# GERMO.net
KiCad netlist of a schematic drawn in EAGLE
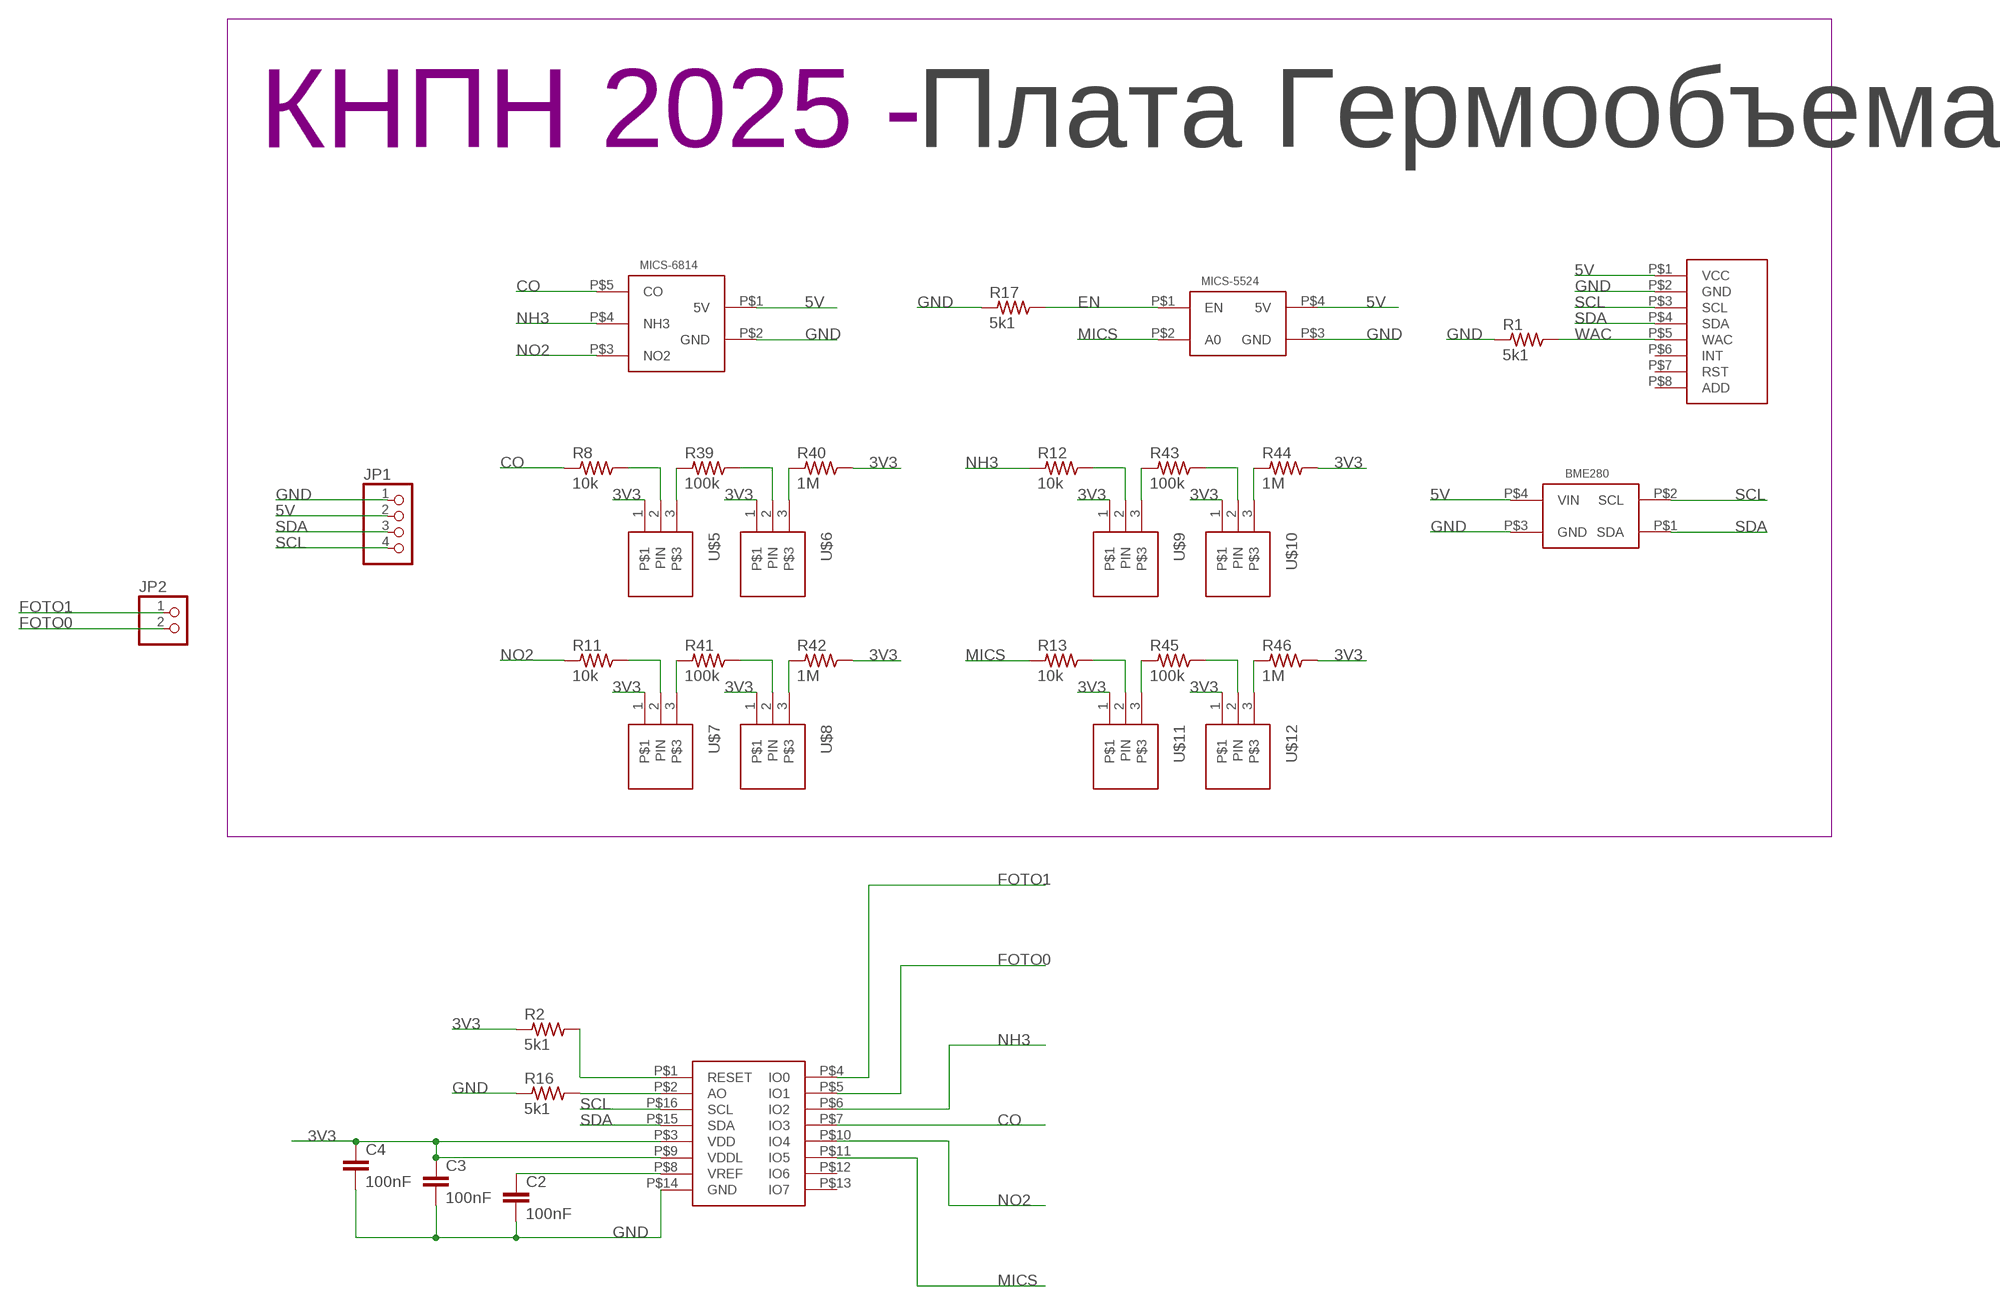
[diagram p0: schematic, sheet 1]

(export (version "E")
  (design (tool "Eeschema 10.0.6"))
  (components
    (comp (ref "BME280")
      (value "BME280BME280-PINS-ONLY")
      (footprint "eagle-import:BME280-PINS-ONLY")
      (libsource (lib "eagle-import") (part "BME280BME280-PINS-ONLY"))
    )
    (comp (ref "C2")
      (value "100nF")
      (footprint "eagle-import:C0603")
      (libsource (lib "eagle-import") (part "C-EUC0603"))
    )
    (comp (ref "C3")
      (value "100nF")
      (footprint "eagle-import:C0603")
      (libsource (lib "eagle-import") (part "C-EUC0603"))
    )
    (comp (ref "C4")
      (value "100nF")
      (footprint "eagle-import:C0603")
      (libsource (lib "eagle-import") (part "C-EUC0603"))
    )
    (comp (ref "CCS811")
      (value "CCS811")
      (footprint "eagle-import:CSS811")
      (libsource (lib "eagle-import") (part "CCS811"))
    )
    (comp (ref "JP1")
      (value "PINHD-1X4")
      (footprint "eagle-import:1X04")
      (libsource (lib "eagle-import") (part "PINHD-1X4"))
    )
    (comp (ref "JP2")
      (value "PINHD-1X2")
      (footprint "eagle-import:1X02")
      (libsource (lib "eagle-import") (part "PINHD-1X2"))
    )
    (comp (ref "MICS-5524")
      (value "MICS_5524")
      (footprint "eagle-import:MICS-5524")
      (libsource (lib "eagle-import") (part "MICS_5524"))
    )
    (comp (ref "MICS-6814")
      (value "MICS-6814")
      (footprint "eagle-import:MICS-6814")
      (libsource (lib "eagle-import") (part "MICS-6814"))
    )
    (comp (ref "R1")
      (value "5k1")
      (footprint "eagle-import:R0603")
      (libsource (lib "eagle-import") (part "R-US_R0603"))
    )
    (comp (ref "R2")
      (value "5k1")
      (footprint "eagle-import:R0603")
      (libsource (lib "eagle-import") (part "R-US_R0603"))
    )
    (comp (ref "R8")
      (value "10k")
      (footprint "eagle-import:R0603")
      (libsource (lib "eagle-import") (part "R-US_R0603"))
    )
    (comp (ref "R11")
      (value "10k")
      (footprint "eagle-import:R0603")
      (libsource (lib "eagle-import") (part "R-US_R0603"))
    )
    (comp (ref "R12")
      (value "10k")
      (footprint "eagle-import:R0603")
      (libsource (lib "eagle-import") (part "R-US_R0603"))
    )
    (comp (ref "R13")
      (value "10k")
      (footprint "eagle-import:R0603")
      (libsource (lib "eagle-import") (part "R-US_R0603"))
    )
    (comp (ref "R16")
      (value "5k1")
      (footprint "eagle-import:R0603")
      (libsource (lib "eagle-import") (part "R-US_R0603"))
    )
    (comp (ref "R17")
      (value "5k1")
      (footprint "eagle-import:R0603")
      (libsource (lib "eagle-import") (part "R-US_R0603"))
    )
    (comp (ref "R39")
      (value "100k")
      (footprint "eagle-import:R0603")
      (libsource (lib "eagle-import") (part "R-US_R0603"))
    )
    (comp (ref "R40")
      (value "1M")
      (footprint "eagle-import:R0603")
      (libsource (lib "eagle-import") (part "R-US_R0603"))
    )
    (comp (ref "R41")
      (value "100k")
      (footprint "eagle-import:R0603")
      (libsource (lib "eagle-import") (part "R-US_R0603"))
    )
    (comp (ref "R42")
      (value "1M")
      (footprint "eagle-import:R0603")
      (libsource (lib "eagle-import") (part "R-US_R0603"))
    )
    (comp (ref "R43")
      (value "100k")
      (footprint "eagle-import:R0603")
      (libsource (lib "eagle-import") (part "R-US_R0603"))
    )
    (comp (ref "R44")
      (value "1M")
      (footprint "eagle-import:R0603")
      (libsource (lib "eagle-import") (part "R-US_R0603"))
    )
    (comp (ref "R45")
      (value "100k")
      (footprint "eagle-import:R0603")
      (libsource (lib "eagle-import") (part "R-US_R0603"))
    )
    (comp (ref "R46")
      (value "1M")
      (footprint "eagle-import:R0603")
      (libsource (lib "eagle-import") (part "R-US_R0603"))
    )
    (comp (ref "U$2")
      (value "Плата Гермообъема")
      (footprint "eagle-import:LOGO")
      (libsource (lib "eagle-import") (part "LOGOPCB-{dblquote}{dblquote}"))
    )
    (comp (ref "U$5")
      (value "CONNECT_3")
      (footprint "eagle-import:CONNECT_3")
      (libsource (lib "eagle-import") (part "CONNECT_3"))
    )
    (comp (ref "U$6")
      (value "CONNECT_3")
      (footprint "eagle-import:CONNECT_3")
      (libsource (lib "eagle-import") (part "CONNECT_3"))
    )
    (comp (ref "U$7")
      (value "CONNECT_3")
      (footprint "eagle-import:CONNECT_3")
      (libsource (lib "eagle-import") (part "CONNECT_3"))
    )
    (comp (ref "U$8")
      (value "CONNECT_3")
      (footprint "eagle-import:CONNECT_3")
      (libsource (lib "eagle-import") (part "CONNECT_3"))
    )
    (comp (ref "U$9")
      (value "CONNECT_3")
      (footprint "eagle-import:CONNECT_3")
      (libsource (lib "eagle-import") (part "CONNECT_3"))
    )
    (comp (ref "U$10")
      (value "CONNECT_3")
      (footprint "eagle-import:CONNECT_3")
      (libsource (lib "eagle-import") (part "CONNECT_3"))
    )
    (comp (ref "U$11")
      (value "CONNECT_3")
      (footprint "eagle-import:CONNECT_3")
      (libsource (lib "eagle-import") (part "CONNECT_3"))
    )
    (comp (ref "U$12")
      (value "CONNECT_3")
      (footprint "eagle-import:CONNECT_3")
      (libsource (lib "eagle-import") (part "CONNECT_3"))
    )
    (comp (ref "U$14")
      (value "AD5593")
      (footprint "eagle-import:AD5593")
      (libsource (lib "eagle-import") (part "AD5593"))
    )
  )
  (nets
    (net (code "1") (name "/3V3") (class "Default")
      (node (ref "C3") (pin "1") (pinfunction "1_1") (pintype "passive"))
      (node (ref "C4") (pin "1") (pinfunction "1_1") (pintype "passive"))
      (node (ref "R2") (pin "2") (pinfunction "2_2") (pintype "passive"))
      (node (ref "R40") (pin "1") (pinfunction "1_1") (pintype "passive"))
      (node (ref "R42") (pin "1") (pinfunction "1_1") (pintype "passive"))
      (node (ref "R44") (pin "1") (pinfunction "1_1") (pintype "passive"))
      (node (ref "R46") (pin "1") (pinfunction "1_1") (pintype "passive"))
      (node (ref "U$10") (pin "1") (pinfunction "P$1_1") (pintype "bidirectional"))
      (node (ref "U$11") (pin "1") (pinfunction "P$1_1") (pintype "bidirectional"))
      (node (ref "U$12") (pin "1") (pinfunction "P$1_1") (pintype "bidirectional"))
      (node (ref "U$14") (pin "P$3") (pinfunction "VDD_P$3") (pintype "bidirectional"))
      (node (ref "U$14") (pin "P$9") (pinfunction "VDDL_P$9") (pintype "bidirectional"))
      (node (ref "U$5") (pin "1") (pinfunction "P$1_1") (pintype "bidirectional"))
      (node (ref "U$6") (pin "1") (pinfunction "P$1_1") (pintype "bidirectional"))
      (node (ref "U$7") (pin "1") (pinfunction "P$1_1") (pintype "bidirectional"))
      (node (ref "U$8") (pin "1") (pinfunction "P$1_1") (pintype "bidirectional"))
      (node (ref "U$9") (pin "1") (pinfunction "P$1_1") (pintype "bidirectional"))
    )
    (net (code "2") (name "/5V") (class "Default")
      (node (ref "BME280") (pin "P$4") (pinfunction "VIN_P$4") (pintype "bidirectional"))
      (node (ref "CCS811") (pin "P$1") (pinfunction "VCC_P$1") (pintype "bidirectional"))
      (node (ref "JP1") (pin "2") (pinfunction "2_2") (pintype "passive"))
      (node (ref "MICS-5524") (pin "P$4") (pinfunction "5V_P$4") (pintype "bidirectional"))
      (node (ref "MICS-6814") (pin "P$1") (pinfunction "5V_P$1") (pintype "bidirectional"))
    )
    (net (code "3") (name "/CO") (class "Default")
      (node (ref "MICS-6814") (pin "P$5") (pinfunction "CO_P$5") (pintype "bidirectional"))
      (node (ref "R8") (pin "2") (pinfunction "2_2") (pintype "passive"))
      (node (ref "U$14") (pin "P$7") (pinfunction "IO3_P$7") (pintype "bidirectional"))
    )
    (net (code "4") (name "/EN") (class "Default")
      (node (ref "MICS-5524") (pin "P$1") (pinfunction "EN_P$1") (pintype "bidirectional"))
      (node (ref "R17") (pin "1") (pinfunction "1_1") (pintype "passive"))
    )
    (net (code "5") (name "/FOTO0") (class "Default")
      (node (ref "JP2") (pin "2") (pinfunction "2_2") (pintype "passive"))
      (node (ref "U$14") (pin "P$5") (pinfunction "IO1_P$5") (pintype "bidirectional"))
    )
    (net (code "6") (name "/FOTO1") (class "Default")
      (node (ref "JP2") (pin "1") (pinfunction "1_1") (pintype "passive"))
      (node (ref "U$14") (pin "P$4") (pinfunction "IO0_P$4") (pintype "bidirectional"))
    )
    (net (code "7") (name "/GND") (class "Default")
      (node (ref "BME280") (pin "P$3") (pinfunction "GND_P$3") (pintype "bidirectional"))
      (node (ref "C2") (pin "2") (pinfunction "2_2") (pintype "passive"))
      (node (ref "C3") (pin "2") (pinfunction "2_2") (pintype "passive"))
      (node (ref "C4") (pin "2") (pinfunction "2_2") (pintype "passive"))
      (node (ref "CCS811") (pin "P$2") (pinfunction "GND_P$2") (pintype "bidirectional"))
      (node (ref "JP1") (pin "1") (pinfunction "1_1") (pintype "passive"))
      (node (ref "MICS-5524") (pin "P$3") (pinfunction "GND_P$3") (pintype "bidirectional"))
      (node (ref "MICS-6814") (pin "P$2") (pinfunction "GND_P$2") (pintype "bidirectional"))
      (node (ref "R1") (pin "2") (pinfunction "2_2") (pintype "passive"))
      (node (ref "R16") (pin "2") (pinfunction "2_2") (pintype "passive"))
      (node (ref "R17") (pin "2") (pinfunction "2_2") (pintype "passive"))
      (node (ref "U$14") (pin "P$14") (pinfunction "GND_P$14") (pintype "bidirectional"))
    )
    (net (code "8") (name "/MICS") (class "Default")
      (node (ref "MICS-5524") (pin "P$2") (pinfunction "A0_P$2") (pintype "bidirectional"))
      (node (ref "R13") (pin "2") (pinfunction "2_2") (pintype "passive"))
      (node (ref "U$14") (pin "P$11") (pinfunction "IO5_P$11") (pintype "bidirectional"))
    )
    (net (code "9") (name "/NH3") (class "Default")
      (node (ref "MICS-6814") (pin "P$4") (pinfunction "NH3_P$4") (pintype "bidirectional"))
      (node (ref "R12") (pin "2") (pinfunction "2_2") (pintype "passive"))
      (node (ref "U$14") (pin "P$6") (pinfunction "IO2_P$6") (pintype "bidirectional"))
    )
    (net (code "10") (name "/NO2") (class "Default")
      (node (ref "MICS-6814") (pin "P$3") (pinfunction "NO2_P$3") (pintype "bidirectional"))
      (node (ref "R11") (pin "2") (pinfunction "2_2") (pintype "passive"))
      (node (ref "U$14") (pin "P$10") (pinfunction "IO4_P$10") (pintype "bidirectional"))
    )
    (net (code "11") (name "/SCL") (class "Default")
      (node (ref "BME280") (pin "P$2") (pinfunction "SCL_P$2") (pintype "bidirectional"))
      (node (ref "CCS811") (pin "P$3") (pinfunction "SCL_P$3") (pintype "bidirectional"))
      (node (ref "JP1") (pin "4") (pinfunction "4_4") (pintype "passive"))
      (node (ref "U$14") (pin "P$16") (pinfunction "SCL_P$16") (pintype "bidirectional"))
    )
    (net (code "12") (name "/SDA") (class "Default")
      (node (ref "BME280") (pin "P$1") (pinfunction "SDA_P$1") (pintype "bidirectional"))
      (node (ref "CCS811") (pin "P$4") (pinfunction "SDA_P$4") (pintype "bidirectional"))
      (node (ref "JP1") (pin "3") (pinfunction "3_3") (pintype "passive"))
      (node (ref "U$14") (pin "P$15") (pinfunction "SDA_P$15") (pintype "bidirectional"))
    )
    (net (code "13") (name "/WAC") (class "Default")
      (node (ref "CCS811") (pin "P$5") (pinfunction "WAC_P$5") (pintype "bidirectional"))
      (node (ref "R1") (pin "1") (pinfunction "1_1") (pintype "passive"))
    )
    (net (code "14") (name "Net-(U$5-P$3)") (class "Default")
      (node (ref "R39") (pin "2") (pinfunction "2_2") (pintype "passive"))
      (node (ref "U$5") (pin "3") (pinfunction "P$3_3") (pintype "bidirectional"))
    )
    (net (code "15") (name "Net-(U$5-PIN)") (class "Default")
      (node (ref "R8") (pin "1") (pinfunction "1_1") (pintype "passive"))
      (node (ref "U$5") (pin "2") (pinfunction "PIN_2") (pintype "bidirectional"))
    )
    (net (code "16") (name "Net-(U$6-P$3)") (class "Default")
      (node (ref "R40") (pin "2") (pinfunction "2_2") (pintype "passive"))
      (node (ref "U$6") (pin "3") (pinfunction "P$3_3") (pintype "bidirectional"))
    )
    (net (code "17") (name "Net-(U$6-PIN)") (class "Default")
      (node (ref "R39") (pin "1") (pinfunction "1_1") (pintype "passive"))
      (node (ref "U$6") (pin "2") (pinfunction "PIN_2") (pintype "bidirectional"))
    )
    (net (code "18") (name "Net-(U$7-P$3)") (class "Default")
      (node (ref "R41") (pin "2") (pinfunction "2_2") (pintype "passive"))
      (node (ref "U$7") (pin "3") (pinfunction "P$3_3") (pintype "bidirectional"))
    )
    (net (code "19") (name "Net-(U$7-PIN)") (class "Default")
      (node (ref "R11") (pin "1") (pinfunction "1_1") (pintype "passive"))
      (node (ref "U$7") (pin "2") (pinfunction "PIN_2") (pintype "bidirectional"))
    )
    (net (code "20") (name "Net-(U$8-P$3)") (class "Default")
      (node (ref "R42") (pin "2") (pinfunction "2_2") (pintype "passive"))
      (node (ref "U$8") (pin "3") (pinfunction "P$3_3") (pintype "bidirectional"))
    )
    (net (code "21") (name "Net-(U$8-PIN)") (class "Default")
      (node (ref "R41") (pin "1") (pinfunction "1_1") (pintype "passive"))
      (node (ref "U$8") (pin "2") (pinfunction "PIN_2") (pintype "bidirectional"))
    )
    (net (code "22") (name "Net-(U$9-P$3)") (class "Default")
      (node (ref "R43") (pin "2") (pinfunction "2_2") (pintype "passive"))
      (node (ref "U$9") (pin "3") (pinfunction "P$3_3") (pintype "bidirectional"))
    )
    (net (code "23") (name "Net-(U$9-PIN)") (class "Default")
      (node (ref "R12") (pin "1") (pinfunction "1_1") (pintype "passive"))
      (node (ref "U$9") (pin "2") (pinfunction "PIN_2") (pintype "bidirectional"))
    )
    (net (code "24") (name "Net-(U$10-P$3)") (class "Default")
      (node (ref "R44") (pin "2") (pinfunction "2_2") (pintype "passive"))
      (node (ref "U$10") (pin "3") (pinfunction "P$3_3") (pintype "bidirectional"))
    )
    (net (code "25") (name "Net-(U$10-PIN)") (class "Default")
      (node (ref "R43") (pin "1") (pinfunction "1_1") (pintype "passive"))
      (node (ref "U$10") (pin "2") (pinfunction "PIN_2") (pintype "bidirectional"))
    )
    (net (code "26") (name "Net-(U$11-P$3)") (class "Default")
      (node (ref "R45") (pin "2") (pinfunction "2_2") (pintype "passive"))
      (node (ref "U$11") (pin "3") (pinfunction "P$3_3") (pintype "bidirectional"))
    )
    (net (code "27") (name "Net-(U$11-PIN)") (class "Default")
      (node (ref "R13") (pin "1") (pinfunction "1_1") (pintype "passive"))
      (node (ref "U$11") (pin "2") (pinfunction "PIN_2") (pintype "bidirectional"))
    )
    (net (code "28") (name "Net-(U$12-P$3)") (class "Default")
      (node (ref "R46") (pin "2") (pinfunction "2_2") (pintype "passive"))
      (node (ref "U$12") (pin "3") (pinfunction "P$3_3") (pintype "bidirectional"))
    )
    (net (code "29") (name "Net-(U$12-PIN)") (class "Default")
      (node (ref "R45") (pin "1") (pinfunction "1_1") (pintype "passive"))
      (node (ref "U$12") (pin "2") (pinfunction "PIN_2") (pintype "bidirectional"))
    )
    (net (code "30") (name "Net-(U$14-AO)") (class "Default")
      (node (ref "R16") (pin "1") (pinfunction "1_1") (pintype "passive"))
      (node (ref "U$14") (pin "P$2") (pinfunction "AO_P$2") (pintype "bidirectional"))
    )
    (net (code "31") (name "Net-(U$14-RESET)") (class "Default")
      (node (ref "R2") (pin "1") (pinfunction "1_1") (pintype "passive"))
      (node (ref "U$14") (pin "P$1") (pinfunction "RESET_P$1") (pintype "bidirectional"))
    )
    (net (code "32") (name "Net-(U$14-VREF)") (class "Default")
      (node (ref "C2") (pin "1") (pinfunction "1_1") (pintype "passive"))
      (node (ref "U$14") (pin "P$8") (pinfunction "VREF_P$8") (pintype "bidirectional"))
    )
    (net (code "33") (name "unconnected-(CCS811-ADD-PadP$8)") (class "Default")
      (node (ref "CCS811") (pin "P$8") (pinfunction "ADD_P$8") (pintype "bidirectional"))
    )
    (net (code "34") (name "unconnected-(CCS811-INT-PadP$6)") (class "Default")
      (node (ref "CCS811") (pin "P$6") (pinfunction "INT_P$6") (pintype "bidirectional"))
    )
    (net (code "35") (name "unconnected-(CCS811-RST-PadP$7)") (class "Default")
      (node (ref "CCS811") (pin "P$7") (pinfunction "RST_P$7") (pintype "bidirectional"))
    )
    (net (code "36") (name "unconnected-(U$14-IO6-PadP$12)") (class "Default")
      (node (ref "U$14") (pin "P$12") (pinfunction "IO6_P$12") (pintype "bidirectional"))
    )
    (net (code "37") (name "unconnected-(U$14-IO7-PadP$13)") (class "Default")
      (node (ref "U$14") (pin "P$13") (pinfunction "IO7_P$13") (pintype "bidirectional"))
    )
  )
)
